# Boost.net
KiCad netlist of a schematic drawn in Altium Designer
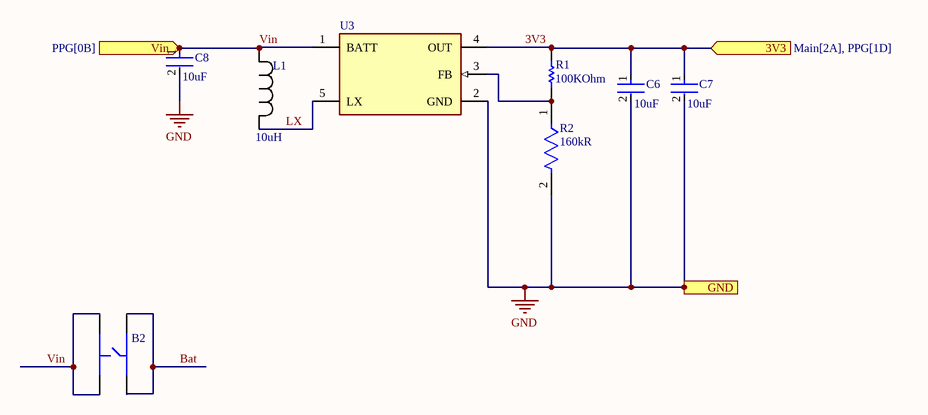
[diagram p0: Boost.SchDoc]

(export (version "E")
  (design (tool "Eeschema 10.0.6"))
  (components
    (comp (ref "B2") (value "TS3425PA") (footprint "TS3425PA") (libsource (lib "Schlib1") (part "TS3425PA")))
    (comp (ref "C6")
      (value "CL10A106MA8NRNC")
      (footprint "FP-CL10-IPC_A")
      (description "Cap Ceramic 10uF 25V X5R ±20% Pad SMD 0603 +85°C T/R")
      (fields (field (name "CAPACITANCE") "10uF") (field (name "TOLERANCE") "20%"))
      (libsource (lib "Altium Content Vault") (part "b4654b650e69147ec39a6b967a45e02"))
    )
    (comp (ref "C7")
      (value "CL10A106MA8NRNC")
      (footprint "FP-CL10-IPC_A")
      (description "Cap Ceramic 10uF 25V X5R ±20% Pad SMD 0603 +85°C T/R")
      (fields (field (name "CAPACITANCE") "10uF") (field (name "TOLERANCE") "20%"))
      (libsource (lib "Altium Content Vault") (part "b4654b650e69147ec39a6b967a45e02"))
    )
    (comp (ref "C8")
      (value "CL10A106MA8NRNC")
      (footprint "FP-CL10-IPC_A")
      (description "Cap Ceramic 10uF 25V X5R ±20% Pad SMD 0603 +85°C T/R")
      (fields (field (name "CAPACITANCE") "10uF") (field (name "TOLERANCE") "20%"))
      (libsource (lib "Altium Content Vault") (part "b4654b650e69147ec39a6b967a45e02"))
    )
    (comp (ref "L1")
      (value "10uH")
      (footprint "SWPA6028S100MT")
      (description "6.0x6.0x2.8 10uH ±20% DCR=94mΩ 1.95A SRF=23MHz 应用:电源")
      (fields
        (field (name "MANUFACTURER") "Sunlord")
        (field (name "MANUFACTURER PART NUMBER") "SWPA6028S100MT")
      )
      (libsource (lib "Schlib1") (part "SWPA6028S100MT"))
    )
    (comp (ref "R1")
      (value "RC1206FR-07100KL")
      (footprint "RESC3116X65X40ML10T20")
      (description "Chip Resistor, 100 KOhm, +/- 1%, 0.25 W, -55 to 155 degC, 1206 (3216 Metric), RoHS, Tape and Reel")
      (fields
        (field (name "RESISTANCE") "100KOhm")
        (field (name "TOLERANCE") "1%")
        (field (name "MANUFACTURER") "Yageo")
      )
      (libsource (lib "Altium Content Vault") (part "RES-2"))
    )
    (comp (ref "R2")
      (value "AC0402FR-07160KL")
      (footprint "FP-AC0402-IPC_B")
      (description "RES 160kΩ ±1% 0.063W 0402")
      (fields
        (field (name "TOLERANCE") "1%")
        (field (name "RESISTANCE") "160kR")
        (field (name "MANUFACTURER") "Yageo")
      )
      (libsource (lib "Altium Content Vault") (part "1029c3af85768c4190bb7ad29bc67b5"))
    )
    (comp (ref "U3")
      (value "MAX1722EZK+T")
      (footprint "FP-Z5-1-IPC_A")
      (description "IC REG BOOST ADJ 400MA TSOT23-5")
      (fields (field (name "MANUFACTURER") "Maxim"))
      (libsource (lib "Altium Content Vault") (part "11a683c76d18c5d219005e2b0e5e8f4"))
    )
  )
  (nets
    (net (code "1") (name "/3V3") (class "Default")
      (node (ref "C6") (pin "1") (pinfunction "1_1") (pintype "passive"))
      (node (ref "C7") (pin "1") (pinfunction "1_1") (pintype "passive"))
      (node (ref "R1") (pin "2") (pinfunction "2_2") (pintype "passive"))
      (node (ref "U3") (pin "4") (pinfunction "OUT_4") (pintype "power_in"))
    )
    (net (code "2") (name "/Bat") (class "Default")
      (node (ref "B2") (pin "3") (pinfunction "3_3") (pintype "passive"))
      (node (ref "B2") (pin "4") (pinfunction "4_4") (pintype "passive"))
    )
    (net (code "3") (name "/LX") (class "Default")
      (node (ref "L1") (pin "1") (pinfunction "1_1") (pintype "passive"))
      (node (ref "U3") (pin "5") (pinfunction "LX_5") (pintype "passive"))
    )
    (net (code "4") (name "/Vin") (class "Default")
      (node (ref "B2") (pin "1") (pinfunction "1_1") (pintype "passive"))
      (node (ref "B2") (pin "2") (pinfunction "2_2") (pintype "passive"))
      (node (ref "C8") (pin "1") (pinfunction "1_1") (pintype "passive"))
      (node (ref "L1") (pin "2") (pinfunction "2_2") (pintype "passive"))
      (node (ref "U3") (pin "1") (pinfunction "BATT_1") (pintype "power_in"))
    )
    (net (code "5") (name "GND") (class "Default")
      (node (ref "C6") (pin "2") (pinfunction "2_2") (pintype "passive"))
      (node (ref "C7") (pin "2") (pinfunction "2_2") (pintype "passive"))
      (node (ref "C8") (pin "2") (pinfunction "2_2") (pintype "passive"))
      (node (ref "R2") (pin "2") (pinfunction "2_2") (pintype "passive"))
      (node (ref "U3") (pin "2") (pinfunction "GND_2") (pintype "power_in"))
    )
    (net (code "6") (name "Net-(U3-FB)") (class "Default")
      (node (ref "R1") (pin "1") (pinfunction "1_1") (pintype "passive"))
      (node (ref "R2") (pin "1") (pinfunction "1_1") (pintype "passive"))
      (node (ref "U3") (pin "3") (pinfunction "FB_3") (pintype "input"))
    )
  )
)
